# 1_P1.net
KiCad netlist of a schematic drawn in Altium Designer
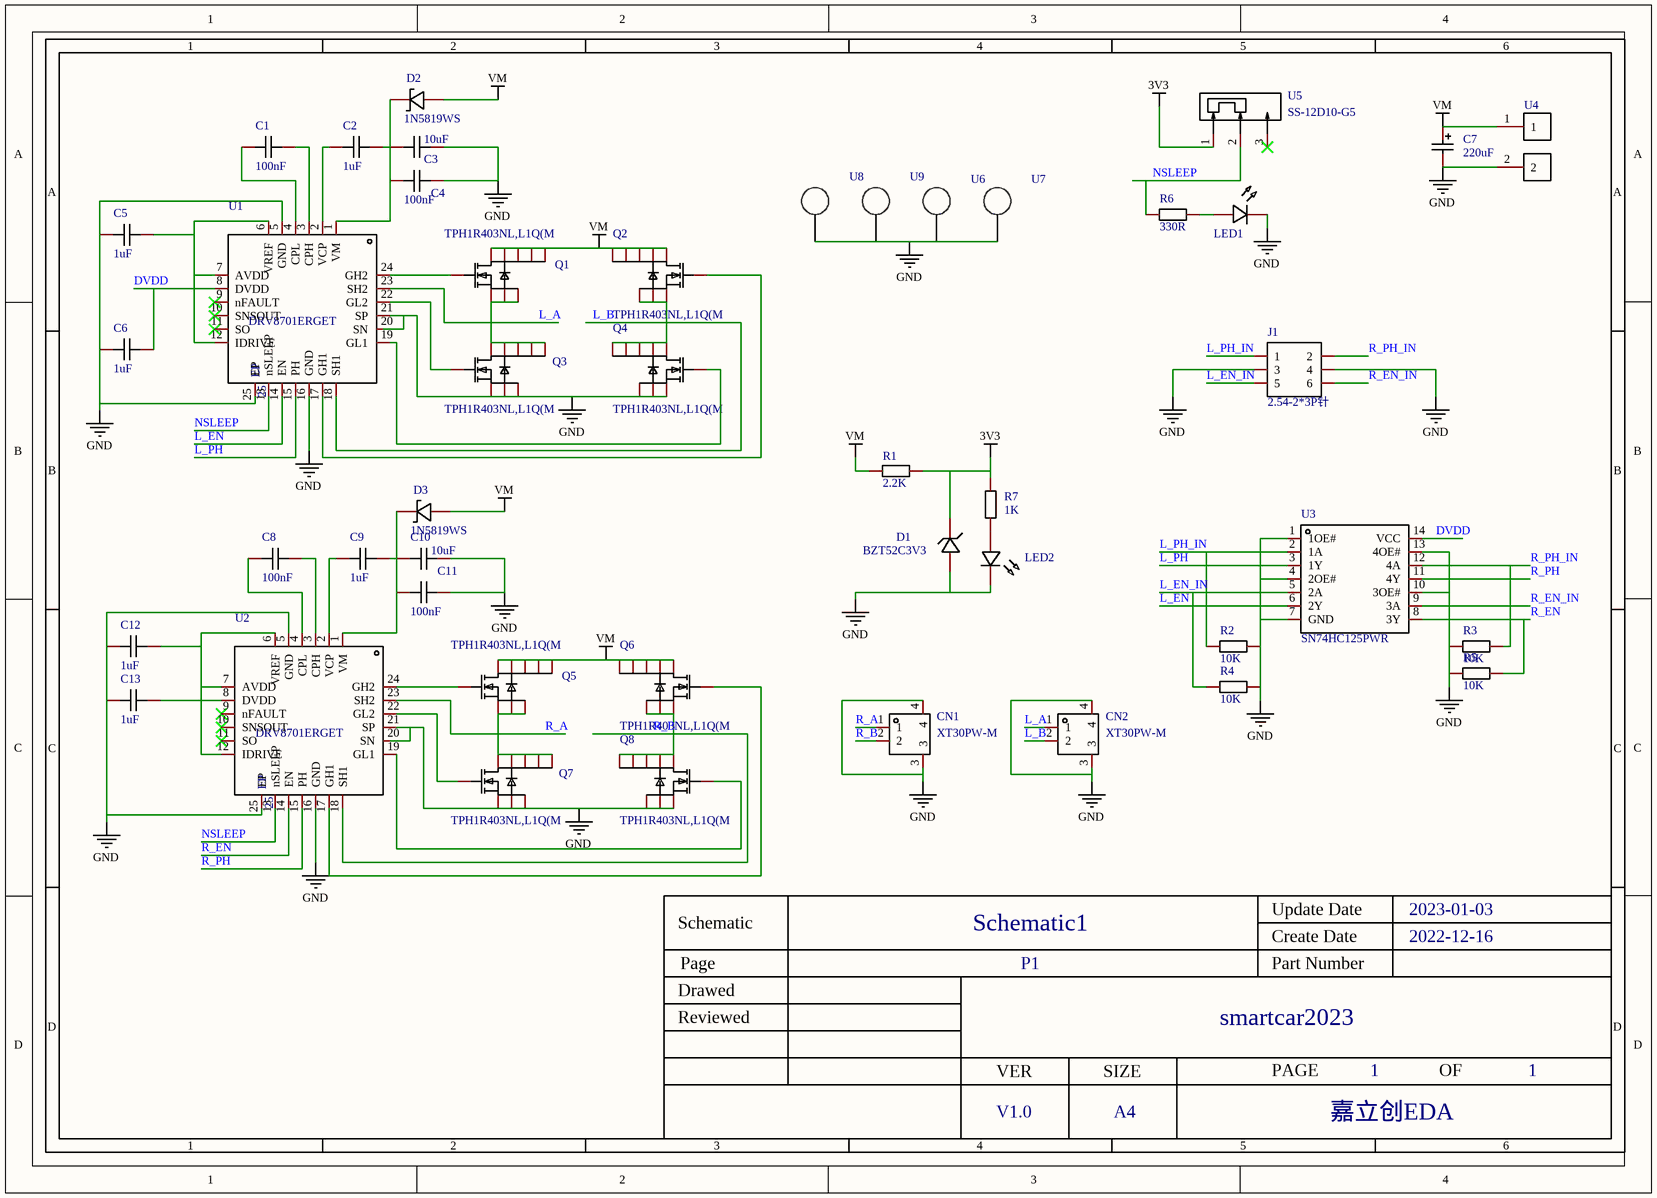
[diagram p0: 1_P1.schdoc]

(export (version "E")
  (design (tool "Eeschema 10.0.6"))
  (components
    (comp (ref "C1")
      (value "100nF")
      (fields (field (name "NAME") "100nF"))
      (libsource (lib "altium-import") (part "root_0_CAP_0603_"))
    )
    (comp (ref "C2")
      (value "1uF")
      (fields (field (name "NAME") "1uF"))
      (libsource (lib "altium-import") (part "root_0_CAP_0603_"))
    )
    (comp (ref "C3")
      (value "10uF")
      (fields (field (name "NAME") "10uF"))
      (libsource (lib "altium-import") (part "root_0_CAP_0603_"))
    )
    (comp (ref "C4")
      (value "100nF")
      (fields (field (name "NAME") "100nF"))
      (libsource (lib "altium-import") (part "root_0_CAP_0603_"))
    )
    (comp (ref "C5")
      (value "1uF")
      (fields (field (name "NAME") "1uF"))
      (libsource (lib "altium-import") (part "root_0_CAP_0603_"))
    )
    (comp (ref "C6")
      (value "1uF")
      (fields (field (name "NAME") "1uF"))
      (libsource (lib "altium-import") (part "root_0_CAP_0603_"))
    )
    (comp (ref "C7")
      (value "220uF")
      (fields
        (field (name "NAME") "220uF")
        (field (name "MANUFACTURER") "ROQANG(容强)")
        (field (name "MANUFACTURER PART") "RVT1E221M0607")
        (field (name "TOLERANCE") "±20%")
      )
      (libsource (lib "altium-import") (part "root_1_RVT1E221M0607_"))
    )
    (comp (ref "C8")
      (value "100nF")
      (fields (field (name "NAME") "100nF"))
      (libsource (lib "altium-import") (part "root_0_CAP_0603_"))
    )
    (comp (ref "C9")
      (value "1uF")
      (fields (field (name "NAME") "1uF"))
      (libsource (lib "altium-import") (part "root_0_CAP_0603_"))
    )
    (comp (ref "C10")
      (value "10uF")
      (fields (field (name "NAME") "10uF"))
      (libsource (lib "altium-import") (part "root_0_CAP_0603_"))
    )
    (comp (ref "C11")
      (value "100nF")
      (fields (field (name "NAME") "100nF"))
      (libsource (lib "altium-import") (part "root_0_CAP_0603_"))
    )
    (comp (ref "C12")
      (value "1uF")
      (fields (field (name "NAME") "1uF"))
      (libsource (lib "altium-import") (part "root_0_CAP_0603_"))
    )
    (comp (ref "C13")
      (value "1uF")
      (fields (field (name "NAME") "1uF"))
      (libsource (lib "altium-import") (part "root_0_CAP_0603_"))
    )
    (comp (ref "CN1")
      (value "XT30PW-M")
      (description "Socket,DCsupply,XT30,male,PIN:2")
      (fields (field (name "NAME") "XT30PW-M") (field (name "MANUFACTURER") "AMASS(艾迈斯)"))
      (libsource (lib "altium-import") (part "root_0_XT30PW-M_"))
    )
    (comp (ref "CN2")
      (value "XT30PW-M")
      (description "Socket,DCsupply,XT30,male,PIN:2")
      (fields (field (name "NAME") "XT30PW-M") (field (name "MANUFACTURER") "AMASS(艾迈斯)"))
      (libsource (lib "altium-import") (part "root_0_XT30PW-M_"))
    )
    (comp (ref "D1")
      (value "BZT52C3V3")
      (description "二极管配置:-;稳压值(标称值):3.3V;稳压值(范围):3.3V~3.5V;功率:500mW;反向电流(Ir):5uA@1V;阻抗(Zzt):95Ω;")
      (fields (field (name "NAME") "BZT52C3V3") (field (name "MANUFACTURER") "YONGYUTAI(永裕泰)"))
      (libsource (lib "altium-import") (part "root_3_BZT52C3V3_"))
    )
    (comp (ref "D2")
      (value "1N5819WS")
      (description "直流反向耐压(Vr):40V;平均整流电流(Io):1A;正向压降(Vf):600mV@1A;")
      (fields (field (name "NAME") "1N5819WS") (field (name "MANUFACTURER") "Hottech(合科泰)"))
      (libsource (lib "altium-import") (part "root_0_1N5819WS_C191023_"))
    )
    (comp (ref "D3")
      (value "1N5819WS")
      (description "直流反向耐压(Vr):40V;平均整流电流(Io):1A;正向压降(Vf):600mV@1A;")
      (fields (field (name "NAME") "1N5819WS") (field (name "MANUFACTURER") "Hottech(合科泰)"))
      (libsource (lib "altium-import") (part "root_0_1N5819WS_C191023_"))
    )
    (comp (ref "J1")
      (value "2.54-2*3P针")
      (fields (field (name "NAME") "2.54-2*3P针") (field (name "MANUFACTURER") "BOOMELE(博穆精密)"))
      (libsource (lib "altium-import") (part "root_0_2.54-2*3P针_"))
    )
    (comp (ref "LED1") (value "LED_0603-R") (libsource (lib "altium-import") (part "root_0_LED_0603-R_")))
    (comp (ref "LED2") (value "LED_0603-R") (libsource (lib "altium-import") (part "root_3_LED_0603-R_")))
    (comp (ref "Q1")
      (value "TPH1R403NL,L1Q(M")
      (fields (field (name "NAME") "TPH1R403NL,L1Q(M") (field (name "MANUFACTURER") "TOSHIBA(东芝)"))
      (libsource (lib "altium-import") (part "root_0_TPH1R403NL,L1Q(M_"))
    )
    (comp (ref "Q2")
      (value "TPH1R403NL,L1Q(M")
      (fields (field (name "NAME") "TPH1R403NL,L1Q(M") (field (name "MANUFACTURER") "TOSHIBA(东芝)"))
      (libsource (lib "altium-import") (part "root_0_mirrored_TPH1R403NL,L1Q(M_"))
    )
    (comp (ref "Q3")
      (value "TPH1R403NL,L1Q(M")
      (fields (field (name "NAME") "TPH1R403NL,L1Q(M") (field (name "MANUFACTURER") "TOSHIBA(东芝)"))
      (libsource (lib "altium-import") (part "root_0_TPH1R403NL,L1Q(M_"))
    )
    (comp (ref "Q4")
      (value "TPH1R403NL,L1Q(M")
      (fields (field (name "NAME") "TPH1R403NL,L1Q(M") (field (name "MANUFACTURER") "TOSHIBA(东芝)"))
      (libsource (lib "altium-import") (part "root_0_mirrored_TPH1R403NL,L1Q(M_"))
    )
    (comp (ref "Q5")
      (value "TPH1R403NL,L1Q(M")
      (fields (field (name "NAME") "TPH1R403NL,L1Q(M") (field (name "MANUFACTURER") "TOSHIBA(东芝)"))
      (libsource (lib "altium-import") (part "root_0_TPH1R403NL,L1Q(M_"))
    )
    (comp (ref "Q6")
      (value "TPH1R403NL,L1Q(M")
      (fields (field (name "NAME") "TPH1R403NL,L1Q(M") (field (name "MANUFACTURER") "TOSHIBA(东芝)"))
      (libsource (lib "altium-import") (part "root_0_mirrored_TPH1R403NL,L1Q(M_"))
    )
    (comp (ref "Q7")
      (value "TPH1R403NL,L1Q(M")
      (fields (field (name "NAME") "TPH1R403NL,L1Q(M") (field (name "MANUFACTURER") "TOSHIBA(东芝)"))
      (libsource (lib "altium-import") (part "root_0_TPH1R403NL,L1Q(M_"))
    )
    (comp (ref "Q8")
      (value "TPH1R403NL,L1Q(M")
      (fields (field (name "NAME") "TPH1R403NL,L1Q(M") (field (name "MANUFACTURER") "TOSHIBA(东芝)"))
      (libsource (lib "altium-import") (part "root_0_mirrored_TPH1R403NL,L1Q(M_"))
    )
    (comp (ref "R1")
      (value "2.2K")
      (fields (field (name "NAME") "2.2K"))
      (libsource (lib "altium-import") (part "root_2_Res_0603_"))
    )
    (comp (ref "R2")
      (value "10K")
      (fields (field (name "NAME") "10K"))
      (libsource (lib "altium-import") (part "root_2_Res_0603_"))
    )
    (comp (ref "R3")
      (value "10K")
      (fields (field (name "NAME") "10K"))
      (libsource (lib "altium-import") (part "root_2_Res_0603_"))
    )
    (comp (ref "R4")
      (value "10K")
      (fields (field (name "NAME") "10K"))
      (libsource (lib "altium-import") (part "root_2_Res_0603_"))
    )
    (comp (ref "R5")
      (value "10K")
      (fields (field (name "NAME") "10K"))
      (libsource (lib "altium-import") (part "root_2_Res_0603_"))
    )
    (comp (ref "R6")
      (value "330R")
      (fields (field (name "NAME") "330R"))
      (libsource (lib "altium-import") (part "root_0_Res_0603_"))
    )
    (comp (ref "R7")
      (value "1K")
      (fields (field (name "NAME") "1K"))
      (libsource (lib "altium-import") (part "root_1_Res_0603_"))
    )
    (comp (ref "U1")
      (value "DRV8701ERGET")
      (description "DRV8701 DRV8701 H 桥栅极驱动器")
      (fields
        (field (name "NAME") "DRV8701ERGET")
        (field (name "MANUFACTURER") "TI(德州仪器)")
        (field (name "NAME_1") "EP")
        (field (name "NUMBER") "25")
      )
      (libsource (lib "altium-import") (part "root_3_DRV8701ERGET_"))
    )
    (comp (ref "U2")
      (value "DRV8701ERGET")
      (description "DRV8701 DRV8701 H 桥栅极驱动器")
      (fields
        (field (name "NAME") "DRV8701ERGET")
        (field (name "MANUFACTURER") "TI(德州仪器)")
        (field (name "NAME_1") "EP")
        (field (name "NUMBER") "25")
      )
      (libsource (lib "altium-import") (part "root_3_DRV8701ERGET_"))
    )
    (comp (ref "U3")
      (value "SN74HC125PWR")
      (description "逻辑电路的归属系列:74HC;逻辑类型:缓冲器，非反向;元件数:4;每元件位数:1;")
      (fields (field (name "NAME") "SN74HC125PWR") (field (name "MANUFACTURER") "TI(德州仪器)"))
      (libsource (lib "altium-import") (part "root_0_SN74HC125PWR_"))
    )
    (comp (ref "U4") (value "电源线焊盘") (libsource (lib "altium-import") (part "root_2_电源线焊盘_")))
    (comp (ref "U5")
      (value "SS-12D10-G5")
      (description "电路结构:单刀双掷;安装方式:直插;开关颜色:黑色;滑钮形状:矩形柱状;引脚样式:PC引脚;开关长度:12.7mm;开关宽度:6.7mm;开关高度:11.3mm;")
      (fields (field (name "NAME") "SS-12D10-G5") (field (name "MANUFACTURER") "DEALON(德艺隆)"))
      (libsource (lib "altium-import") (part "root_0_SS-12D10-G5_"))
    )
    (comp (ref "U6") (value "M3-MountSlot") (libsource (lib "altium-import") (part "root_1_M3-MountSlot_")))
    (comp (ref "U7") (value "M3-MountSlot") (libsource (lib "altium-import") (part "root_1_M3-MountSlot_")))
    (comp (ref "U8") (value "M3-MountSlot") (libsource (lib "altium-import") (part "root_1_M3-MountSlot_")))
    (comp (ref "U9") (value "M3-MountSlot") (libsource (lib "altium-import") (part "root_1_M3-MountSlot_")))
  )
  (nets
    (net (code "1") (name "/DVDD") (class "Default")
      (node (ref "C6") (pin "2") (pinfunction "2_2") (pintype "passive"))
      (node (ref "U1") (pin "8") (pinfunction "DVDD_8") (pintype "passive"))
      (node (ref "U3") (pin "14") (pinfunction "VCC_14") (pintype "passive"))
    )
    (net (code "2") (name "/L_A") (class "Default")
      (node (ref "CN2") (pin "1") (pinfunction "1_1") (pintype "passive"))
      (node (ref "Q1") (pin "1") (pinfunction "S_1") (pintype "passive"))
      (node (ref "Q1") (pin "2") (pinfunction "S_2") (pintype "passive"))
      (node (ref "Q1") (pin "3") (pinfunction "S_3") (pintype "passive"))
      (node (ref "Q3") (pin "5") (pinfunction "D_5") (pintype "passive"))
      (node (ref "Q3") (pin "6") (pinfunction "D_6") (pintype "passive"))
      (node (ref "Q3") (pin "7") (pinfunction "D_7") (pintype "passive"))
      (node (ref "Q3") (pin "8") (pinfunction "D_8") (pintype "passive"))
      (node (ref "Q3") (pin "9") (pinfunction "D_9") (pintype "passive"))
      (node (ref "U1") (pin "23") (pinfunction "SH2_23") (pintype "passive"))
    )
    (net (code "3") (name "/L_B") (class "Default")
      (node (ref "CN2") (pin "2") (pinfunction "2_2") (pintype "passive"))
      (node (ref "Q2") (pin "1") (pinfunction "S_1") (pintype "passive"))
      (node (ref "Q2") (pin "2") (pinfunction "S_2") (pintype "passive"))
      (node (ref "Q2") (pin "3") (pinfunction "S_3") (pintype "passive"))
      (node (ref "Q4") (pin "5") (pinfunction "D_5") (pintype "passive"))
      (node (ref "Q4") (pin "6") (pinfunction "D_6") (pintype "passive"))
      (node (ref "Q4") (pin "7") (pinfunction "D_7") (pintype "passive"))
      (node (ref "Q4") (pin "8") (pinfunction "D_8") (pintype "passive"))
      (node (ref "Q4") (pin "9") (pinfunction "D_9") (pintype "passive"))
      (node (ref "U1") (pin "18") (pinfunction "SH1_18") (pintype "passive"))
    )
    (net (code "4") (name "/L_EN") (class "Default")
      (node (ref "U1") (pin "14") (pinfunction "EN_14") (pintype "passive"))
      (node (ref "U3") (pin "6") (pinfunction "2Y_6") (pintype "passive"))
    )
    (net (code "5") (name "/L_EN_IN") (class "Default")
      (node (ref "J1") (pin "5") (pinfunction "5_5") (pintype "passive"))
      (node (ref "R4") (pin "2") (pinfunction "2_2") (pintype "passive"))
      (node (ref "U3") (pin "5") (pinfunction "2A_5") (pintype "passive"))
    )
    (net (code "6") (name "/L_PH") (class "Default")
      (node (ref "U1") (pin "15") (pinfunction "PH_15") (pintype "passive"))
      (node (ref "U3") (pin "3") (pinfunction "1Y_3") (pintype "passive"))
    )
    (net (code "7") (name "/L_PH_IN") (class "Default")
      (node (ref "J1") (pin "1") (pinfunction "1_1") (pintype "passive"))
      (node (ref "R2") (pin "2") (pinfunction "2_2") (pintype "passive"))
      (node (ref "U3") (pin "2") (pinfunction "1A_2") (pintype "passive"))
    )
    (net (code "8") (name "/NSLEEP") (class "Default")
      (node (ref "R6") (pin "1") (pinfunction "1_1") (pintype "passive"))
      (node (ref "U1") (pin "13") (pinfunction "nSLEEP_13") (pintype "passive"))
      (node (ref "U2") (pin "13") (pinfunction "nSLEEP_13") (pintype "passive"))
      (node (ref "U5") (pin "2") (pinfunction "2_2") (pintype "passive"))
    )
    (net (code "9") (name "/R_A") (class "Default")
      (node (ref "CN1") (pin "1") (pinfunction "1_1") (pintype "passive"))
      (node (ref "Q5") (pin "1") (pinfunction "S_1") (pintype "passive"))
      (node (ref "Q5") (pin "2") (pinfunction "S_2") (pintype "passive"))
      (node (ref "Q5") (pin "3") (pinfunction "S_3") (pintype "passive"))
      (node (ref "Q7") (pin "5") (pinfunction "D_5") (pintype "passive"))
      (node (ref "Q7") (pin "6") (pinfunction "D_6") (pintype "passive"))
      (node (ref "Q7") (pin "7") (pinfunction "D_7") (pintype "passive"))
      (node (ref "Q7") (pin "8") (pinfunction "D_8") (pintype "passive"))
      (node (ref "Q7") (pin "9") (pinfunction "D_9") (pintype "passive"))
      (node (ref "U2") (pin "23") (pinfunction "SH2_23") (pintype "passive"))
    )
    (net (code "10") (name "/R_B") (class "Default")
      (node (ref "CN1") (pin "2") (pinfunction "2_2") (pintype "passive"))
      (node (ref "Q6") (pin "1") (pinfunction "S_1") (pintype "passive"))
      (node (ref "Q6") (pin "2") (pinfunction "S_2") (pintype "passive"))
      (node (ref "Q6") (pin "3") (pinfunction "S_3") (pintype "passive"))
      (node (ref "Q8") (pin "5") (pinfunction "D_5") (pintype "passive"))
      (node (ref "Q8") (pin "6") (pinfunction "D_6") (pintype "passive"))
      (node (ref "Q8") (pin "7") (pinfunction "D_7") (pintype "passive"))
      (node (ref "Q8") (pin "8") (pinfunction "D_8") (pintype "passive"))
      (node (ref "Q8") (pin "9") (pinfunction "D_9") (pintype "passive"))
      (node (ref "U2") (pin "18") (pinfunction "SH1_18") (pintype "passive"))
    )
    (net (code "11") (name "/R_EN") (class "Default")
      (node (ref "R5") (pin "1") (pinfunction "1_1") (pintype "passive"))
      (node (ref "U2") (pin "14") (pinfunction "EN_14") (pintype "passive"))
      (node (ref "U3") (pin "8") (pinfunction "3Y_8") (pintype "passive"))
    )
    (net (code "12") (name "/R_EN_IN") (class "Default")
      (node (ref "J1") (pin "6") (pinfunction "6_6") (pintype "passive"))
      (node (ref "U3") (pin "9") (pinfunction "3A_9") (pintype "passive"))
    )
    (net (code "13") (name "/R_PH") (class "Default")
      (node (ref "U2") (pin "15") (pinfunction "PH_15") (pintype "passive"))
      (node (ref "U3") (pin "11") (pinfunction "4Y_11") (pintype "passive"))
    )
    (net (code "14") (name "/R_PH_IN") (class "Default")
      (node (ref "J1") (pin "2") (pinfunction "2_2") (pintype "passive"))
      (node (ref "R3") (pin "1") (pinfunction "1_1") (pintype "passive"))
      (node (ref "U3") (pin "12") (pinfunction "4A_12") (pintype "passive"))
    )
    (net (code "15") (name "3V3") (class "Default")
      (node (ref "D1") (pin "1") (pinfunction "1_1") (pintype "passive"))
      (node (ref "R1") (pin "1") (pinfunction "1_1") (pintype "passive"))
      (node (ref "R7") (pin "2") (pinfunction "2_2") (pintype "passive"))
      (node (ref "U5") (pin "1") (pinfunction "1_1") (pintype "passive"))
    )
    (net (code "16") (name "GND") (class "Default")
      (node (ref "C10") (pin "2") (pinfunction "2_2") (pintype "passive"))
      (node (ref "C11") (pin "2") (pinfunction "2_2") (pintype "passive"))
      (node (ref "C12") (pin "1") (pinfunction "1_1") (pintype "passive"))
      (node (ref "C13") (pin "1") (pinfunction "1_1") (pintype "passive"))
      (node (ref "C3") (pin "2") (pinfunction "2_2") (pintype "passive"))
      (node (ref "C4") (pin "2") (pinfunction "2_2") (pintype "passive"))
      (node (ref "C5") (pin "1") (pinfunction "1_1") (pintype "passive"))
      (node (ref "C6") (pin "1") (pinfunction "1_1") (pintype "passive"))
      (node (ref "C7") (pin "2") (pinfunction "2_2") (pintype "passive"))
      (node (ref "CN1") (pin "3") (pinfunction "3_3") (pintype "passive"))
      (node (ref "CN1") (pin "4") (pinfunction "4_4") (pintype "passive"))
      (node (ref "CN2") (pin "3") (pinfunction "3_3") (pintype "passive"))
      (node (ref "CN2") (pin "4") (pinfunction "4_4") (pintype "passive"))
      (node (ref "D1") (pin "2") (pinfunction "2_2") (pintype "passive"))
      (node (ref "J1") (pin "3") (pinfunction "3_3") (pintype "passive"))
      (node (ref "J1") (pin "4") (pinfunction "4_4") (pintype "passive"))
      (node (ref "LED1") (pin "1") (pinfunction "C_1") (pintype "passive"))
      (node (ref "LED2") (pin "1") (pinfunction "C_1") (pintype "passive"))
      (node (ref "Q3") (pin "1") (pinfunction "S_1") (pintype "passive"))
      (node (ref "Q3") (pin "2") (pinfunction "S_2") (pintype "passive"))
      (node (ref "Q3") (pin "3") (pinfunction "S_3") (pintype "passive"))
      (node (ref "Q4") (pin "1") (pinfunction "S_1") (pintype "passive"))
      (node (ref "Q4") (pin "2") (pinfunction "S_2") (pintype "passive"))
      (node (ref "Q4") (pin "3") (pinfunction "S_3") (pintype "passive"))
      (node (ref "Q7") (pin "1") (pinfunction "S_1") (pintype "passive"))
      (node (ref "Q7") (pin "2") (pinfunction "S_2") (pintype "passive"))
      (node (ref "Q7") (pin "3") (pinfunction "S_3") (pintype "passive"))
      (node (ref "Q8") (pin "1") (pinfunction "S_1") (pintype "passive"))
      (node (ref "Q8") (pin "2") (pinfunction "S_2") (pintype "passive"))
      (node (ref "Q8") (pin "3") (pinfunction "S_3") (pintype "passive"))
      (node (ref "R2") (pin "1") (pinfunction "1_1") (pintype "passive"))
      (node (ref "R3") (pin "2") (pinfunction "2_2") (pintype "passive"))
      (node (ref "R4") (pin "1") (pinfunction "1_1") (pintype "passive"))
      (node (ref "R5") (pin "2") (pinfunction "2_2") (pintype "passive"))
      (node (ref "U1") (pin "16") (pinfunction "GND_16") (pintype "passive"))
      (node (ref "U1") (pin "20") (pinfunction "SN_20") (pintype "passive"))
      (node (ref "U1") (pin "21") (pinfunction "SP_21") (pintype "passive"))
      (node (ref "U1") (pin "25") (pinfunction "EP_25") (pintype "passive"))
      (node (ref "U1") (pin "5") (pinfunction "GND_5") (pintype "passive"))
      (node (ref "U2") (pin "16") (pinfunction "GND_16") (pintype "passive"))
      (node (ref "U2") (pin "20") (pinfunction "SN_20") (pintype "passive"))
      (node (ref "U2") (pin "21") (pinfunction "SP_21") (pintype "passive"))
      (node (ref "U2") (pin "25") (pinfunction "EP_25") (pintype "passive"))
      (node (ref "U2") (pin "5") (pinfunction "GND_5") (pintype "passive"))
      (node (ref "U3") (pin "1") (pinfunction "1OE#_1") (pintype "passive"))
      (node (ref "U3") (pin "10") (pinfunction "3OE#_10") (pintype "passive"))
      (node (ref "U3") (pin "13") (pinfunction "4OE#_13") (pintype "passive"))
      (node (ref "U3") (pin "4") (pinfunction "2OE#_4") (pintype "passive"))
      (node (ref "U3") (pin "7") (pinfunction "GND_7") (pintype "passive"))
      (node (ref "U4") (pin "2") (pinfunction "2_2") (pintype "passive"))
      (node (ref "U6") (pin "1") (pinfunction "1_1") (pintype "passive"))
      (node (ref "U7") (pin "1") (pinfunction "1_1") (pintype "passive"))
      (node (ref "U8") (pin "1") (pinfunction "1_1") (pintype "passive"))
      (node (ref "U9") (pin "1") (pinfunction "1_1") (pintype "passive"))
    )
    (net (code "17") (name "Net-(D2-C)") (class "Default")
      (node (ref "C2") (pin "2") (pinfunction "2_2") (pintype "passive"))
      (node (ref "C3") (pin "1") (pinfunction "1_1") (pintype "passive"))
      (node (ref "C4") (pin "1") (pinfunction "1_1") (pintype "passive"))
      (node (ref "D2") (pin "1") (pinfunction "C_1") (pintype "passive"))
      (node (ref "U1") (pin "1") (pinfunction "VM_1") (pintype "passive"))
    )
    (net (code "18") (name "Net-(D3-C)") (class "Default")
      (node (ref "C10") (pin "1") (pinfunction "1_1") (pintype "passive"))
      (node (ref "C11") (pin "1") (pinfunction "1_1") (pintype "passive"))
      (node (ref "C9") (pin "2") (pinfunction "2_2") (pintype "passive"))
      (node (ref "D3") (pin "1") (pinfunction "C_1") (pintype "passive"))
      (node (ref "U2") (pin "1") (pinfunction "VM_1") (pintype "passive"))
    )
    (net (code "19") (name "Net-(LED1-A)") (class "Default")
      (node (ref "LED1") (pin "2") (pinfunction "A_2") (pintype "passive"))
      (node (ref "R6") (pin "2") (pinfunction "2_2") (pintype "passive"))
    )
    (net (code "20") (name "Net-(LED2-A)") (class "Default")
      (node (ref "LED2") (pin "2") (pinfunction "A_2") (pintype "passive"))
      (node (ref "R7") (pin "1") (pinfunction "1_1") (pintype "passive"))
    )
    (net (code "21") (name "Net-(Q1-G)") (class "Default")
      (node (ref "Q1") (pin "4") (pinfunction "G_4") (pintype "passive"))
      (node (ref "U1") (pin "24") (pinfunction "GH2_24") (pintype "passive"))
    )
    (net (code "22") (name "Net-(Q2-G)") (class "Default")
      (node (ref "Q2") (pin "4") (pinfunction "G_4") (pintype "passive"))
      (node (ref "U1") (pin "17") (pinfunction "GH1_17") (pintype "passive"))
    )
    (net (code "23") (name "Net-(Q3-G)") (class "Default")
      (node (ref "Q3") (pin "4") (pinfunction "G_4") (pintype "passive"))
      (node (ref "U1") (pin "22") (pinfunction "GL2_22") (pintype "passive"))
    )
    (net (code "24") (name "Net-(Q4-G)") (class "Default")
      (node (ref "Q4") (pin "4") (pinfunction "G_4") (pintype "passive"))
      (node (ref "U1") (pin "19") (pinfunction "GL1_19") (pintype "passive"))
    )
    (net (code "25") (name "Net-(Q5-G)") (class "Default")
      (node (ref "Q5") (pin "4") (pinfunction "G_4") (pintype "passive"))
      (node (ref "U2") (pin "24") (pinfunction "GH2_24") (pintype "passive"))
    )
    (net (code "26") (name "Net-(Q6-G)") (class "Default")
      (node (ref "Q6") (pin "4") (pinfunction "G_4") (pintype "passive"))
      (node (ref "U2") (pin "17") (pinfunction "GH1_17") (pintype "passive"))
    )
    (net (code "27") (name "Net-(Q7-G)") (class "Default")
      (node (ref "Q7") (pin "4") (pinfunction "G_4") (pintype "passive"))
      (node (ref "U2") (pin "22") (pinfunction "GL2_22") (pintype "passive"))
    )
    (net (code "28") (name "Net-(Q8-G)") (class "Default")
      (node (ref "Q8") (pin "4") (pinfunction "G_4") (pintype "passive"))
      (node (ref "U2") (pin "19") (pinfunction "GL1_19") (pintype "passive"))
    )
    (net (code "29") (name "Net-(U1-AVDD)") (class "Default")
      (node (ref "C5") (pin "2") (pinfunction "2_2") (pintype "passive"))
      (node (ref "U1") (pin "12") (pinfunction "IDRIVE_12") (pintype "passive"))
      (node (ref "U1") (pin "6") (pinfunction "VREF_6") (pintype "passive"))
      (node (ref "U1") (pin "7") (pinfunction "AVDD_7") (pintype "passive"))
    )
    (net (code "30") (name "Net-(U1-CPH)") (class "Default")
      (node (ref "C1") (pin "2") (pinfunction "2_2") (pintype "passive"))
      (node (ref "U1") (pin "3") (pinfunction "CPH_3") (pintype "passive"))
    )
    (net (code "31") (name "Net-(U1-CPL)") (class "Default")
      (node (ref "C1") (pin "1") (pinfunction "1_1") (pintype "passive"))
      (node (ref "U1") (pin "4") (pinfunction "CPL_4") (pintype "passive"))
    )
    (net (code "32") (name "Net-(U1-VCP)") (class "Default")
      (node (ref "C2") (pin "1") (pinfunction "1_1") (pintype "passive"))
      (node (ref "U1") (pin "2") (pinfunction "VCP_2") (pintype "passive"))
    )
    (net (code "33") (name "Net-(U2-AVDD)") (class "Default")
      (node (ref "C12") (pin "2") (pinfunction "2_2") (pintype "passive"))
      (node (ref "U2") (pin "12") (pinfunction "IDRIVE_12") (pintype "passive"))
      (node (ref "U2") (pin "6") (pinfunction "VREF_6") (pintype "passive"))
      (node (ref "U2") (pin "7") (pinfunction "AVDD_7") (pintype "passive"))
    )
    (net (code "34") (name "Net-(U2-CPH)") (class "Default")
      (node (ref "C8") (pin "2") (pinfunction "2_2") (pintype "passive"))
      (node (ref "U2") (pin "3") (pinfunction "CPH_3") (pintype "passive"))
    )
    (net (code "35") (name "Net-(U2-CPL)") (class "Default")
      (node (ref "C8") (pin "1") (pinfunction "1_1") (pintype "passive"))
      (node (ref "U2") (pin "4") (pinfunction "CPL_4") (pintype "passive"))
    )
    (net (code "36") (name "Net-(U2-DVDD)") (class "Default")
      (node (ref "C13") (pin "2") (pinfunction "2_2") (pintype "passive"))
      (node (ref "U2") (pin "8") (pinfunction "DVDD_8") (pintype "passive"))
    )
    (net (code "37") (name "Net-(U2-VCP)") (class "Default")
      (node (ref "C9") (pin "1") (pinfunction "1_1") (pintype "passive"))
      (node (ref "U2") (pin "2") (pinfunction "VCP_2") (pintype "passive"))
    )
    (net (code "38") (name "VM") (class "Default")
      (node (ref "C7") (pin "1") (pinfunction "1_1") (pintype "passive"))
      (node (ref "D2") (pin "2") (pinfunction "A_2") (pintype "passive"))
      (node (ref "D3") (pin "2") (pinfunction "A_2") (pintype "passive"))
      (node (ref "Q1") (pin "5") (pinfunction "D_5") (pintype "passive"))
      (node (ref "Q1") (pin "6") (pinfunction "D_6") (pintype "passive"))
      (node (ref "Q1") (pin "7") (pinfunction "D_7") (pintype "passive"))
      (node (ref "Q1") (pin "8") (pinfunction "D_8") (pintype "passive"))
      (node (ref "Q1") (pin "9") (pinfunction "D_9") (pintype "passive"))
      (node (ref "Q2") (pin "5") (pinfunction "D_5") (pintype "passive"))
      (node (ref "Q2") (pin "6") (pinfunction "D_6") (pintype "passive"))
      (node (ref "Q2") (pin "7") (pinfunction "D_7") (pintype "passive"))
      (node (ref "Q2") (pin "8") (pinfunction "D_8") (pintype "passive"))
      (node (ref "Q2") (pin "9") (pinfunction "D_9") (pintype "passive"))
      (node (ref "Q5") (pin "5") (pinfunction "D_5") (pintype "passive"))
      (node (ref "Q5") (pin "6") (pinfunction "D_6") (pintype "passive"))
      (node (ref "Q5") (pin "7") (pinfunction "D_7") (pintype "passive"))
      (node (ref "Q5") (pin "8") (pinfunction "D_8") (pintype "passive"))
      (node (ref "Q5") (pin "9") (pinfunction "D_9") (pintype "passive"))
      (node (ref "Q6") (pin "5") (pinfunction "D_5") (pintype "passive"))
      (node (ref "Q6") (pin "6") (pinfunction "D_6") (pintype "passive"))
      (node (ref "Q6") (pin "7") (pinfunction "D_7") (pintype "passive"))
      (node (ref "Q6") (pin "8") (pinfunction "D_8") (pintype "passive"))
      (node (ref "Q6") (pin "9") (pinfunction "D_9") (pintype "passive"))
      (node (ref "R1") (pin "2") (pinfunction "2_2") (pintype "passive"))
      (node (ref "U4") (pin "1") (pinfunction "1_1") (pintype "passive"))
    )
    (net (code "39") (name "unconnected-(U1-SNSOUT-Pad10)") (class "Default")
      (node (ref "U1") (pin "10") (pinfunction "SNSOUT_10") (pintype "passive+no_connect"))
    )
    (net (code "40") (name "unconnected-(U1-SO-Pad11)") (class "Default")
      (node (ref "U1") (pin "11") (pinfunction "SO_11") (pintype "passive+no_connect"))
    )
    (net (code "41") (name "unconnected-(U1-nFAULT-Pad9)") (class "Default")
      (node (ref "U1") (pin "9") (pinfunction "nFAULT_9") (pintype "passive+no_connect"))
    )
    (net (code "42") (name "unconnected-(U2-SNSOUT-Pad10)") (class "Default")
      (node (ref "U2") (pin "10") (pinfunction "SNSOUT_10") (pintype "passive+no_connect"))
    )
    (net (code "43") (name "unconnected-(U2-SO-Pad11)") (class "Default")
      (node (ref "U2") (pin "11") (pinfunction "SO_11") (pintype "passive+no_connect"))
    )
    (net (code "44") (name "unconnected-(U2-nFAULT-Pad9)") (class "Default")
      (node (ref "U2") (pin "9") (pinfunction "nFAULT_9") (pintype "passive+no_connect"))
    )
    (net (code "45") (name "unconnected-(U5-Pad3)") (class "Default")
      (node (ref "U5") (pin "3") (pinfunction "3_3") (pintype "passive+no_connect"))
    )
  )
)
